# MRCS-Off-Hook-Detector.net
KiCad netlist of a schematic drawn in EAGLE
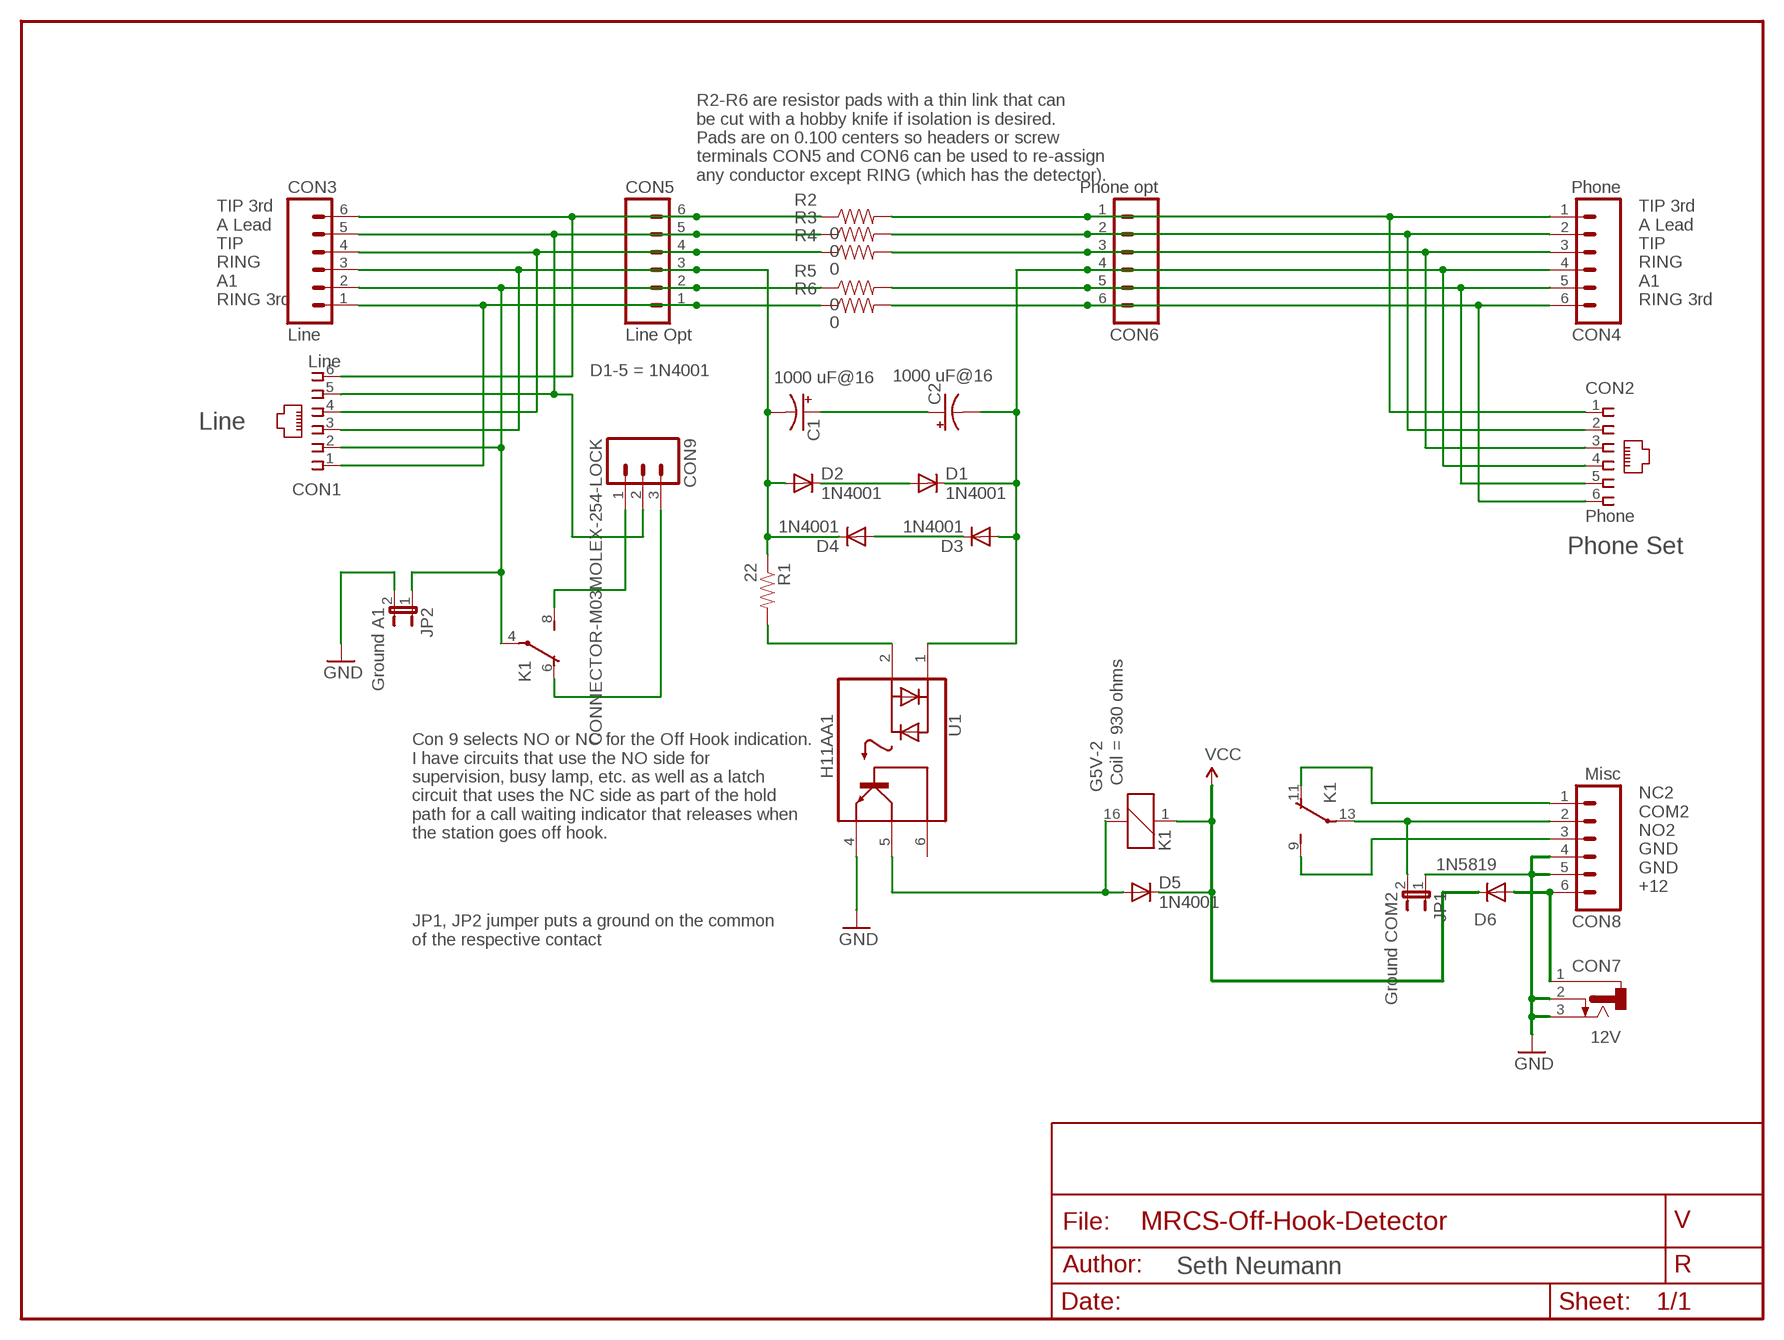
[diagram p0: schematic, sheet 1]

(export (version "E")
  (design (tool "Eeschema 10.0.6"))
  (components
    (comp (ref "C1")
      (value "1000 uF@16")
      (footprint "eagle-import:E3,5-8")
      (libsource (lib "eagle-import") (part "CPOL-USE3.5-8"))
    )
    (comp (ref "C2")
      (value "1000 uF@16")
      (footprint "eagle-import:E3,5-8")
      (libsource (lib "eagle-import") (part "CPOL-USE3.5-8"))
    )
    (comp (ref "CON1")
      (value "Line")
      (footprint "eagle-import:RJ25-INVERTED")
      (libsource (lib "eagle-import") (part "CONNECTOR-RJ25-43860-2-MOLEX"))
    )
    (comp (ref "CON2")
      (value "Phone")
      (footprint "eagle-import:RJ25-INVERTED")
      (libsource (lib "eagle-import") (part "CONNECTOR-RJ25-43860-2-MOLEX"))
    )
    (comp (ref "CON3")
      (value "Line")
      (footprint "eagle-import:1X06_LOCK")
      (libsource (lib "eagle-import") (part "CONNECTOR-M06LOCK"))
    )
    (comp (ref "CON4")
      (value "Phone")
      (footprint "eagle-import:1X06_LOCK")
      (libsource (lib "eagle-import") (part "CONNECTOR-M06LOCK"))
    )
    (comp (ref "CON5")
      (value "Line Opt")
      (footprint "eagle-import:1X06_LOCK")
      (libsource (lib "eagle-import") (part "CONNECTOR-M06LOCK"))
    )
    (comp (ref "CON6")
      (value "Phone opt")
      (footprint "eagle-import:1X06_LOCK")
      (libsource (lib "eagle-import") (part "CONNECTOR-M06LOCK"))
    )
    (comp (ref "CON7")
      (value "12V")
      (footprint "eagle-import:DCJ0202")
      (libsource (lib "eagle-import") (part "CONNECTOR-DC-POWER-RA"))
    )
    (comp (ref "CON8")
      (value "Misc")
      (footprint "eagle-import:1X06_LOCK")
      (libsource (lib "eagle-import") (part "CONNECTOR-M06LOCK"))
    )
    (comp (ref "CON9")
      (value "CONNECTOR-M03MOLEX-254-LOCK")
      (footprint "eagle-import:MOLEX-1X3_LOCK")
      (libsource (lib "eagle-import") (part "CONNECTOR-M03MOLEX-254-LOCK"))
    )
    (comp (ref "D1")
      (value "1N4001")
      (footprint "eagle-import:DIODE-1N4001")
      (libsource (lib "eagle-import") (part "DIODEPTH"))
    )
    (comp (ref "D2")
      (value "1N4001")
      (footprint "eagle-import:DIODE-1N4001")
      (libsource (lib "eagle-import") (part "DIODEPTH"))
    )
    (comp (ref "D3")
      (value "1N4001")
      (footprint "eagle-import:DIODE-1N4001")
      (libsource (lib "eagle-import") (part "DIODEPTH"))
    )
    (comp (ref "D4")
      (value "1N4001")
      (footprint "eagle-import:DIODE-1N4001")
      (libsource (lib "eagle-import") (part "DIODEPTH"))
    )
    (comp (ref "D5")
      (value "1N4001")
      (footprint "eagle-import:DIODE-1N4001")
      (libsource (lib "eagle-import") (part "DIODEPTH"))
    )
    (comp (ref "D6")
      (value "1N5819")
      (footprint "eagle-import:DIODE-1N4001")
      (libsource (lib "eagle-import") (part "DIODEPTH"))
    )
    (comp (ref "JP1")
      (value "Ground COM2")
      (footprint "eagle-import:1X02")
      (libsource (lib "eagle-import") (part "JUMPER-2PTH"))
    )
    (comp (ref "JP2")
      (value "Ground A1")
      (footprint "eagle-import:1X02")
      (libsource (lib "eagle-import") (part "JUMPER-2PTH"))
    )
    (comp (ref "K1")
      (value "G5V-2")
      (footprint "eagle-import:G5V-2")
      (fields (field (name "MPN") "G5V-2 5DC"))
      (libsource (lib "eagle-import") (part "G5V-2"))
    )
    (comp (ref "R1")
      (value "22")
      (footprint "eagle-import:AXIAL-0.4-RES")
      (libsource (lib "eagle-import") (part "RPTH04"))
    )
    (comp (ref "R2")
      (value "0")
      (footprint "eagle-import:CUT-R")
      (libsource (lib "eagle-import") (part "RPTH-R0"))
    )
    (comp (ref "R3")
      (value "0")
      (footprint "eagle-import:CUT-R")
      (libsource (lib "eagle-import") (part "RPTH-R0"))
    )
    (comp (ref "R4")
      (value "0")
      (footprint "eagle-import:CUT-R")
      (libsource (lib "eagle-import") (part "RPTH-R0"))
    )
    (comp (ref "R5")
      (value "0")
      (footprint "eagle-import:CUT-R")
      (libsource (lib "eagle-import") (part "RPTH-R0"))
    )
    (comp (ref "R6")
      (value "0")
      (footprint "eagle-import:CUT-R")
      (libsource (lib "eagle-import") (part "RPTH-R0"))
    )
    (comp (ref "U1")
      (value "H11AA1")
      (footprint "eagle-import:DIP762W50P254L730H410Q6")
      (fields (field (name "MF") "Vishay"))
      (libsource (lib "eagle-import") (part "H11AA1"))
    )
  )
  (nets
    (net (code "1") (name "GND") (class "Default")
      (node (ref "CON7") (pin "2") (pinfunction "2_2") (pintype "passive"))
      (node (ref "CON7") (pin "3") (pinfunction "3_3") (pintype "passive"))
      (node (ref "CON8") (pin "4") (pinfunction "4_4") (pintype "passive"))
      (node (ref "CON8") (pin "5") (pinfunction "5_5") (pintype "passive"))
      (node (ref "JP1") (pin "1") (pinfunction "1_1") (pintype "passive"))
      (node (ref "JP2") (pin "2") (pinfunction "2_2") (pintype "passive"))
      (node (ref "U1") (pin "4") (pinfunction "E_4") (pintype "passive"))
    )
    (net (code "2") (name "Net-(C1-Pad+)") (class "Default")
      (node (ref "C1") (pin "+") (pinfunction "+_+") (pintype "passive"))
      (node (ref "C2") (pin "+") (pinfunction "+_+") (pintype "passive"))
    )
    (net (code "3") (name "Net-(CON7-Pad1)") (class "Default")
      (node (ref "CON7") (pin "1") (pinfunction "1_1") (pintype "passive"))
      (node (ref "CON8") (pin "6") (pinfunction "6_6") (pintype "passive"))
      (node (ref "D6") (pin "A") (pinfunction "A_A") (pintype "passive"))
    )
    (net (code "4") (name "Net-(D1-PadA)") (class "Default")
      (node (ref "D1") (pin "A") (pinfunction "A_A") (pintype "passive"))
      (node (ref "D2") (pin "C") (pinfunction "C_C") (pintype "passive"))
    )
    (net (code "5") (name "Net-(D3-PadC)") (class "Default")
      (node (ref "D3") (pin "C") (pinfunction "C_C") (pintype "passive"))
      (node (ref "D4") (pin "A") (pinfunction "A_A") (pintype "passive"))
    )
    (net (code "6") (name "Net-(K1A-O)") (class "Default")
      (node (ref "CON9") (pin "3") (pinfunction "3_3") (pintype "passive"))
      (node (ref "K1") (pin "6") (pinfunction "O_6") (pintype "passive"))
    )
    (net (code "7") (name "Net-(K1A-P)") (class "Default")
      (node (ref "CON1") (pin "2") (pinfunction "2_2") (pintype "passive"))
      (node (ref "CON3") (pin "2") (pinfunction "2_2") (pintype "passive"))
      (node (ref "CON5") (pin "2") (pinfunction "2_2") (pintype "passive"))
      (node (ref "JP2") (pin "1") (pinfunction "1_1") (pintype "passive"))
      (node (ref "K1") (pin "4") (pinfunction "P_4") (pintype "passive"))
      (node (ref "R5") (pin "P2") (pinfunction "1_P2") (pintype "passive"))
    )
    (net (code "8") (name "Net-(K1A-S)") (class "Default")
      (node (ref "CON9") (pin "1") (pinfunction "1_1") (pintype "passive"))
      (node (ref "K1") (pin "8") (pinfunction "S_8") (pintype "passive"))
    )
    (net (code "9") (name "Net-(K1B-O)") (class "Default")
      (node (ref "CON8") (pin "1") (pinfunction "1_1") (pintype "passive"))
      (node (ref "K1") (pin "11") (pinfunction "O_11") (pintype "passive"))
    )
    (net (code "10") (name "Net-(K1B-P)") (class "Default")
      (node (ref "CON8") (pin "2") (pinfunction "2_2") (pintype "passive"))
      (node (ref "JP1") (pin "2") (pinfunction "2_2") (pintype "passive"))
      (node (ref "K1") (pin "13") (pinfunction "P_13") (pintype "passive"))
    )
    (net (code "11") (name "Net-(K1B-S)") (class "Default")
      (node (ref "CON8") (pin "3") (pinfunction "3_3") (pintype "passive"))
      (node (ref "K1") (pin "9") (pinfunction "S_9") (pintype "passive"))
    )
    (net (code "12") (name "Net-(K1C-2)") (class "Default")
      (node (ref "D5") (pin "A") (pinfunction "A_A") (pintype "passive"))
      (node (ref "K1") (pin "16") (pinfunction "2_16") (pintype "passive"))
      (node (ref "U1") (pin "5") (pinfunction "C_5") (pintype "passive"))
    )
    (net (code "13") (name "Net-(R1-1)") (class "Default")
      (node (ref "C1") (pin "-") (pinfunction "-_-") (pintype "passive"))
      (node (ref "CON1") (pin "3") (pinfunction "3_3") (pintype "passive"))
      (node (ref "CON3") (pin "3") (pinfunction "3_3") (pintype "passive"))
      (node (ref "CON5") (pin "3") (pinfunction "3_3") (pintype "passive"))
      (node (ref "D2") (pin "A") (pinfunction "A_A") (pintype "passive"))
      (node (ref "D4") (pin "C") (pinfunction "C_C") (pintype "passive"))
      (node (ref "R1") (pin "P$1") (pinfunction "1_P$1") (pintype "passive"))
    )
    (net (code "14") (name "Net-(R1-2)") (class "Default")
      (node (ref "R1") (pin "P$2") (pinfunction "2_P$2") (pintype "passive"))
      (node (ref "U1") (pin "2") (pinfunction "C/A_2") (pintype "passive"))
    )
    (net (code "15") (name "Net-(R2-1)") (class "Default")
      (node (ref "CON1") (pin "6") (pinfunction "6_6") (pintype "passive"))
      (node (ref "CON3") (pin "6") (pinfunction "6_6") (pintype "passive"))
      (node (ref "CON5") (pin "6") (pinfunction "6_6") (pintype "passive"))
      (node (ref "R2") (pin "P2") (pinfunction "1_P2") (pintype "passive"))
    )
    (net (code "16") (name "Net-(R2-2)") (class "Default")
      (node (ref "CON2") (pin "1") (pinfunction "1_1") (pintype "passive"))
      (node (ref "CON4") (pin "1") (pinfunction "1_1") (pintype "passive"))
      (node (ref "CON6") (pin "1") (pinfunction "1_1") (pintype "passive"))
      (node (ref "R2") (pin "P1") (pinfunction "2_P1") (pintype "passive"))
    )
    (net (code "17") (name "Net-(R3-1)") (class "Default")
      (node (ref "CON1") (pin "5") (pinfunction "5_5") (pintype "passive"))
      (node (ref "CON3") (pin "5") (pinfunction "5_5") (pintype "passive"))
      (node (ref "CON5") (pin "5") (pinfunction "5_5") (pintype "passive"))
      (node (ref "CON9") (pin "2") (pinfunction "2_2") (pintype "passive"))
      (node (ref "R3") (pin "P2") (pinfunction "1_P2") (pintype "passive"))
    )
    (net (code "18") (name "Net-(R3-2)") (class "Default")
      (node (ref "CON2") (pin "2") (pinfunction "2_2") (pintype "passive"))
      (node (ref "CON4") (pin "2") (pinfunction "2_2") (pintype "passive"))
      (node (ref "CON6") (pin "2") (pinfunction "2_2") (pintype "passive"))
      (node (ref "R3") (pin "P1") (pinfunction "2_P1") (pintype "passive"))
    )
    (net (code "19") (name "Net-(R4-1)") (class "Default")
      (node (ref "CON1") (pin "4") (pinfunction "4_4") (pintype "passive"))
      (node (ref "CON3") (pin "4") (pinfunction "4_4") (pintype "passive"))
      (node (ref "CON5") (pin "4") (pinfunction "4_4") (pintype "passive"))
      (node (ref "R4") (pin "P2") (pinfunction "1_P2") (pintype "passive"))
    )
    (net (code "20") (name "Net-(R4-2)") (class "Default")
      (node (ref "CON2") (pin "3") (pinfunction "3_3") (pintype "passive"))
      (node (ref "CON4") (pin "3") (pinfunction "3_3") (pintype "passive"))
      (node (ref "CON6") (pin "3") (pinfunction "3_3") (pintype "passive"))
      (node (ref "R4") (pin "P1") (pinfunction "2_P1") (pintype "passive"))
    )
    (net (code "21") (name "Net-(R5-2)") (class "Default")
      (node (ref "CON2") (pin "5") (pinfunction "5_5") (pintype "passive"))
      (node (ref "CON4") (pin "5") (pinfunction "5_5") (pintype "passive"))
      (node (ref "CON6") (pin "5") (pinfunction "5_5") (pintype "passive"))
      (node (ref "R5") (pin "P1") (pinfunction "2_P1") (pintype "passive"))
    )
    (net (code "22") (name "Net-(R6-1)") (class "Default")
      (node (ref "CON1") (pin "1") (pinfunction "1_1") (pintype "passive"))
      (node (ref "CON3") (pin "1") (pinfunction "1_1") (pintype "passive"))
      (node (ref "CON5") (pin "1") (pinfunction "1_1") (pintype "passive"))
      (node (ref "R6") (pin "P2") (pinfunction "1_P2") (pintype "passive"))
    )
    (net (code "23") (name "Net-(R6-2)") (class "Default")
      (node (ref "CON2") (pin "6") (pinfunction "6_6") (pintype "passive"))
      (node (ref "CON4") (pin "6") (pinfunction "6_6") (pintype "passive"))
      (node (ref "CON6") (pin "6") (pinfunction "6_6") (pintype "passive"))
      (node (ref "R6") (pin "P1") (pinfunction "2_P1") (pintype "passive"))
    )
    (net (code "24") (name "Net-(U1-A{slash}C)") (class "Default")
      (node (ref "C2") (pin "-") (pinfunction "-_-") (pintype "passive"))
      (node (ref "CON2") (pin "4") (pinfunction "4_4") (pintype "passive"))
      (node (ref "CON4") (pin "4") (pinfunction "4_4") (pintype "passive"))
      (node (ref "CON6") (pin "4") (pinfunction "4_4") (pintype "passive"))
      (node (ref "D1") (pin "C") (pinfunction "C_C") (pintype "passive"))
      (node (ref "D3") (pin "A") (pinfunction "A_A") (pintype "passive"))
      (node (ref "U1") (pin "1") (pinfunction "A/C_1") (pintype "passive"))
    )
    (net (code "25") (name "VCC") (class "Default")
      (node (ref "D5") (pin "C") (pinfunction "C_C") (pintype "passive"))
      (node (ref "D6") (pin "C") (pinfunction "C_C") (pintype "passive"))
      (node (ref "K1") (pin "1") (pinfunction "1_1") (pintype "passive"))
    )
    (net (code "26") (name "unconnected-(U1-B-Pad6)") (class "Default")
      (node (ref "U1") (pin "6") (pinfunction "B_6") (pintype "passive"))
    )
  )
)
